# M7050C.net
KiCad netlist of a schematic drawn in EAGLE
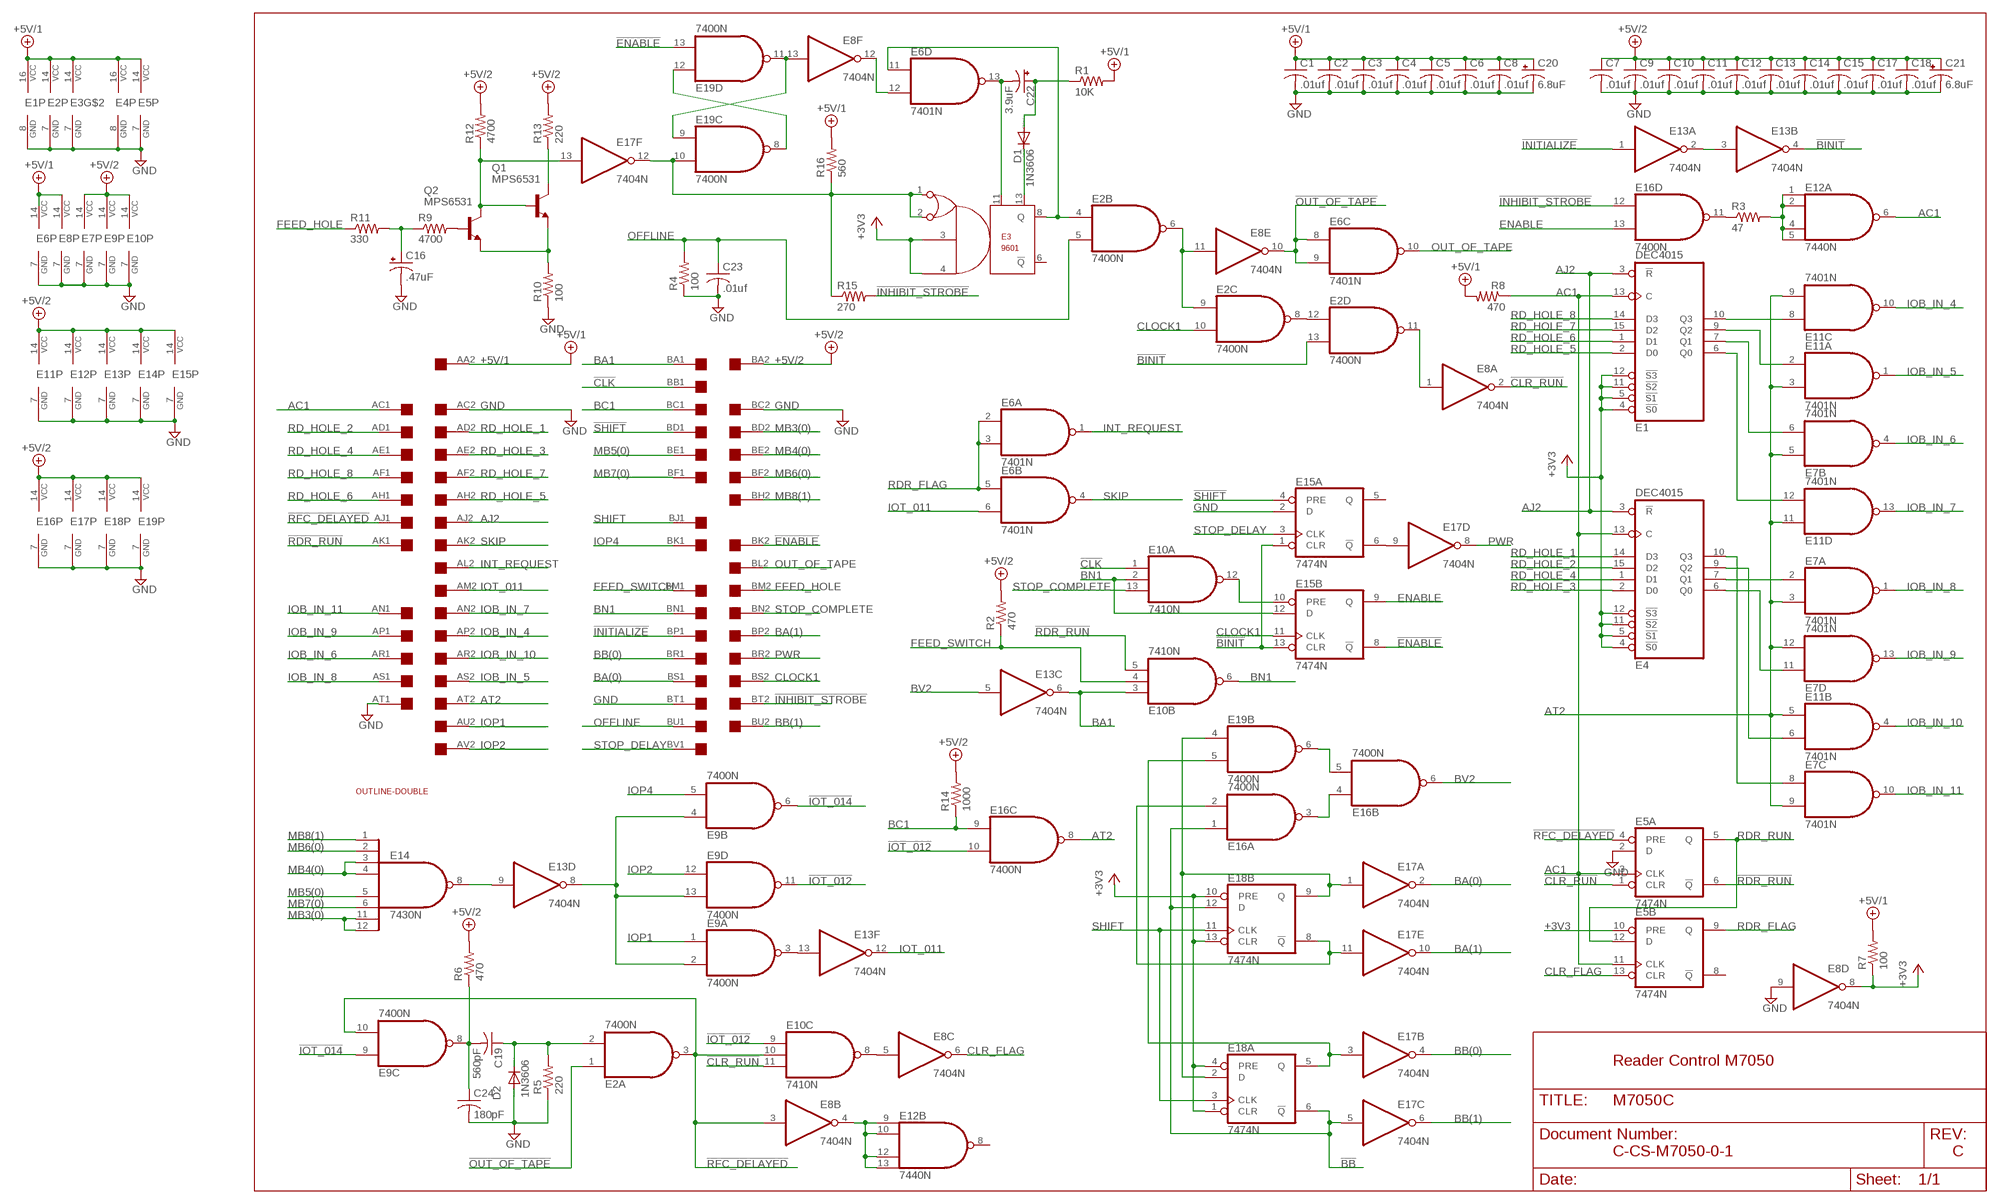
[diagram p0: schematic, sheet 1]

(export (version "E")
  (design (tool "Eeschema 10.0.6"))
  (components
    (comp (ref "C1")
      (value ".01uf")
      (footprint "eagle-import:C075-032X103")
      (libsource (lib "eagle-import") (part "C-US075-032X103"))
    )
    (comp (ref "C2")
      (value ".01uf")
      (footprint "eagle-import:C075-032X103")
      (libsource (lib "eagle-import") (part "C-US075-032X103"))
    )
    (comp (ref "C3")
      (value ".01uf")
      (footprint "eagle-import:C075-032X103")
      (libsource (lib "eagle-import") (part "C-US075-032X103"))
    )
    (comp (ref "C4")
      (value ".01uf")
      (footprint "eagle-import:C075-032X103")
      (libsource (lib "eagle-import") (part "C-US075-032X103"))
    )
    (comp (ref "C5")
      (value ".01uf")
      (footprint "eagle-import:C075-032X103")
      (libsource (lib "eagle-import") (part "C-US075-032X103"))
    )
    (comp (ref "C6")
      (value ".01uf")
      (footprint "eagle-import:C075-032X103")
      (libsource (lib "eagle-import") (part "C-US075-032X103"))
    )
    (comp (ref "C7")
      (value ".01uf")
      (footprint "eagle-import:C075-032X103")
      (libsource (lib "eagle-import") (part "C-US075-032X103"))
    )
    (comp (ref "C8")
      (value ".01uf")
      (footprint "eagle-import:C075-032X103")
      (libsource (lib "eagle-import") (part "C-US075-032X103"))
    )
    (comp (ref "C9")
      (value ".01uf")
      (footprint "eagle-import:C075-032X103")
      (libsource (lib "eagle-import") (part "C-US075-032X103"))
    )
    (comp (ref "C10")
      (value ".01uf")
      (footprint "eagle-import:C075-032X103")
      (libsource (lib "eagle-import") (part "C-US075-032X103"))
    )
    (comp (ref "C11")
      (value ".01uf")
      (footprint "eagle-import:C075-032X103")
      (libsource (lib "eagle-import") (part "C-US075-032X103"))
    )
    (comp (ref "C12")
      (value ".01uf")
      (footprint "eagle-import:C075-032X103")
      (libsource (lib "eagle-import") (part "C-US075-032X103"))
    )
    (comp (ref "C13")
      (value ".01uf")
      (footprint "eagle-import:C075-032X103")
      (libsource (lib "eagle-import") (part "C-US075-032X103"))
    )
    (comp (ref "C14")
      (value ".01uf")
      (footprint "eagle-import:C075-032X103")
      (libsource (lib "eagle-import") (part "C-US075-032X103"))
    )
    (comp (ref "C15")
      (value ".01uf")
      (footprint "eagle-import:C075-032X103")
      (libsource (lib "eagle-import") (part "C-US075-032X103"))
    )
    (comp (ref "C16")
      (value ".47uF")
      (footprint "eagle-import:E15-5")
      (libsource (lib "eagle-import") (part "CPOL-USE15-5AXIAL"))
    )
    (comp (ref "C17")
      (value ".01uf")
      (footprint "eagle-import:C075-032X103")
      (libsource (lib "eagle-import") (part "C-US075-032X103"))
    )
    (comp (ref "C18")
      (value ".01uf")
      (footprint "eagle-import:C075-032X103")
      (libsource (lib "eagle-import") (part "C-US075-032X103"))
    )
    (comp (ref "C19")
      (value "560pF")
      (footprint "eagle-import:C075-032X103")
      (libsource (lib "eagle-import") (part "C-US075-032X103"))
    )
    (comp (ref "C20")
      (value "6.8uF")
      (footprint "eagle-import:E12-8")
      (libsource (lib "eagle-import") (part "CPOL-USE20-8AXIAL"))
    )
    (comp (ref "C21")
      (value "6.8uF")
      (footprint "eagle-import:E12-8")
      (libsource (lib "eagle-import") (part "CPOL-USE20-8AXIAL"))
    )
    (comp (ref "C22")
      (value "3.9uF")
      (footprint "eagle-import:E15-5")
      (libsource (lib "eagle-import") (part "rcl_CPOL-USE15-5AXIAL"))
    )
    (comp (ref "C23")
      (value ".01uf")
      (footprint "eagle-import:C075-032X103")
      (libsource (lib "eagle-import") (part "C-US075-032X103"))
    )
    (comp (ref "C24")
      (value "180pF")
      (footprint "eagle-import:C075-032X103")
      (libsource (lib "eagle-import") (part "C-US075-032X103"))
    )
    (comp (ref "D1")
      (value "1N3606")
      (footprint "eagle-import:DO35-10")
      (libsource (lib "eagle-import") (part "1N4148DO35-10"))
    )
    (comp (ref "D2")
      (value "1N3606")
      (footprint "eagle-import:DO35-10")
      (libsource (lib "eagle-import") (part "1N4148DO35-10"))
    )
    (comp (ref "E1")
      (value "DEC4015")
      (footprint "eagle-import:DIL16")
      (libsource (lib "eagle-import") (part "DEC4015"))
    )
    (comp (ref "E2")
      (value "7400N")
      (footprint "eagle-import:DIL14")
      (libsource (lib "eagle-import") (part "7400N"))
    )
    (comp (ref "E3")
      (value "9601")
      (footprint "eagle-import:DIL14")
      (libsource (lib "eagle-import") (part "9601"))
    )
    (comp (ref "E4")
      (value "DEC4015")
      (footprint "eagle-import:DIL16")
      (libsource (lib "eagle-import") (part "DEC4015"))
    )
    (comp (ref "E5")
      (value "7474N")
      (footprint "eagle-import:DIL14")
      (libsource (lib "eagle-import") (part "7474NS"))
    )
    (comp (ref "E6")
      (value "7401N")
      (footprint "eagle-import:DIL14")
      (libsource (lib "eagle-import") (part "7401NLS"))
    )
    (comp (ref "E7")
      (value "7401N")
      (footprint "eagle-import:DIL14")
      (libsource (lib "eagle-import") (part "7401NLS"))
    )
    (comp (ref "E8")
      (value "7404N")
      (footprint "eagle-import:DIL14")
      (libsource (lib "eagle-import") (part "7404N"))
    )
    (comp (ref "E9")
      (value "7400N")
      (footprint "eagle-import:DIL14")
      (libsource (lib "eagle-import") (part "7400N"))
    )
    (comp (ref "E10")
      (value "7410N")
      (footprint "eagle-import:DIL14")
      (libsource (lib "eagle-import") (part "7410N"))
    )
    (comp (ref "E11")
      (value "7401N")
      (footprint "eagle-import:DIL14")
      (libsource (lib "eagle-import") (part "7401NLS"))
    )
    (comp (ref "E12")
      (value "7440N")
      (footprint "eagle-import:DIL14")
      (libsource (lib "eagle-import") (part "7420NS"))
    )
    (comp (ref "E13")
      (value "7404N")
      (footprint "eagle-import:DIL14")
      (libsource (lib "eagle-import") (part "7404N"))
    )
    (comp (ref "E14")
      (value "7430N")
      (footprint "eagle-import:DIL14")
      (libsource (lib "eagle-import") (part "7430N"))
    )
    (comp (ref "E15")
      (value "7474N")
      (footprint "eagle-import:DIL14")
      (libsource (lib "eagle-import") (part "7474NS"))
    )
    (comp (ref "E16")
      (value "7400N")
      (footprint "eagle-import:DIL14")
      (libsource (lib "eagle-import") (part "7400N"))
    )
    (comp (ref "E17")
      (value "7404N")
      (footprint "eagle-import:DIL14")
      (libsource (lib "eagle-import") (part "7404N"))
    )
    (comp (ref "E18")
      (value "7474N")
      (footprint "eagle-import:DIL14")
      (libsource (lib "eagle-import") (part "7474NS"))
    )
    (comp (ref "E19")
      (value "7400N")
      (footprint "eagle-import:DIL14")
      (libsource (lib "eagle-import") (part "7400N"))
    )
    (comp (ref "Q1")
      (value "MPS6531")
      (footprint "eagle-import:TO5")
      (libsource (lib "eagle-import") (part "2N2102"))
    )
    (comp (ref "Q2")
      (value "MPS6531")
      (footprint "eagle-import:TO5")
      (libsource (lib "eagle-import") (part "2N2102"))
    )
    (comp (ref "R1")
      (value "10K")
      (footprint "eagle-import:0207_10")
      (libsource (lib "eagle-import") (part "R-US_0207/10"))
    )
    (comp (ref "R2")
      (value "470")
      (footprint "eagle-import:0207_10")
      (libsource (lib "eagle-import") (part "R-US_0207/10"))
    )
    (comp (ref "R3")
      (value "47")
      (footprint "eagle-import:0207_10")
      (libsource (lib "eagle-import") (part "R-US_0207/10"))
    )
    (comp (ref "R4")
      (value "100")
      (footprint "eagle-import:0207_10")
      (libsource (lib "eagle-import") (part "R-US_0207/10"))
    )
    (comp (ref "R5")
      (value "220")
      (footprint "eagle-import:0207_10")
      (libsource (lib "eagle-import") (part "R-US_0207/10"))
    )
    (comp (ref "R6")
      (value "470")
      (footprint "eagle-import:0207_10")
      (libsource (lib "eagle-import") (part "R-US_0207/10"))
    )
    (comp (ref "R7")
      (value "100")
      (footprint "eagle-import:0207_10")
      (libsource (lib "eagle-import") (part "R-US_0207/10"))
    )
    (comp (ref "R8")
      (value "470")
      (footprint "eagle-import:0207_10")
      (libsource (lib "eagle-import") (part "R-US_0207/10"))
    )
    (comp (ref "R9")
      (value "4700")
      (footprint "eagle-import:0207_10")
      (libsource (lib "eagle-import") (part "R-US_0207/10"))
    )
    (comp (ref "R10")
      (value "100")
      (footprint "eagle-import:0207_10")
      (libsource (lib "eagle-import") (part "R-US_0207/10"))
    )
    (comp (ref "R11")
      (value "330")
      (footprint "eagle-import:0207_10")
      (libsource (lib "eagle-import") (part "R-US_0207/10"))
    )
    (comp (ref "R12")
      (value "4700")
      (footprint "eagle-import:0207_10")
      (libsource (lib "eagle-import") (part "R-US_0207/10"))
    )
    (comp (ref "R13")
      (value "220")
      (footprint "eagle-import:0207_10")
      (libsource (lib "eagle-import") (part "R-US_0207/10"))
    )
    (comp (ref "R14")
      (value "1000")
      (footprint "eagle-import:0207_10")
      (libsource (lib "eagle-import") (part "R-US_0207/10"))
    )
    (comp (ref "R15")
      (value "270")
      (footprint "eagle-import:0207_10")
      (libsource (lib "eagle-import") (part "R-US_0207/10"))
    )
    (comp (ref "R16")
      (value "560")
      (footprint "eagle-import:0207_10")
      (libsource (lib "eagle-import") (part "R-US_0207/10"))
    )
    (comp (ref "U$5")
      (value "DOUBLE")
      (footprint "eagle-import:EDGE-CON4")
      (libsource (lib "eagle-import") (part "DOUBLE"))
    )
    (comp (ref "U$6")
      (value "OUTLINE-DOUBLE")
      (footprint "eagle-import:DOUBLE")
      (libsource (lib "eagle-import") (part "OUTLINE-DOUBLE"))
    )
  )
  (nets
    (net (code "1") (name "+3V3") (class "Default")
      (node (ref "E1") (pin "11") (pinfunction "~{S2}_11") (pintype "input"))
      (node (ref "E1") (pin "12") (pinfunction "~{S3}_12") (pintype "input"))
      (node (ref "E1") (pin "4") (pinfunction "~{S0}_4") (pintype "input"))
      (node (ref "E1") (pin "5") (pinfunction "~{S1}_5") (pintype "input"))
      (node (ref "E18") (pin "1") (pinfunction "CLR_1") (pintype "input"))
      (node (ref "E18") (pin "10") (pinfunction "PRE_10") (pintype "input"))
      (node (ref "E18") (pin "13") (pinfunction "CLR_13") (pintype "input"))
      (node (ref "E18") (pin "4") (pinfunction "PRE_4") (pintype "input"))
      (node (ref "E3") (pin "3") (pinfunction "P$3_3") (pintype "input"))
      (node (ref "E3") (pin "4") (pinfunction "P$4_4") (pintype "input"))
      (node (ref "E4") (pin "11") (pinfunction "~{S2}_11") (pintype "input"))
      (node (ref "E4") (pin "12") (pinfunction "~{S3}_12") (pintype "input"))
      (node (ref "E4") (pin "4") (pinfunction "~{S0}_4") (pintype "input"))
      (node (ref "E4") (pin "5") (pinfunction "~{S1}_5") (pintype "input"))
      (node (ref "E5") (pin "10") (pinfunction "PRE_10") (pintype "input"))
      (node (ref "E8") (pin "8") (pinfunction "O_8") (pintype "output"))
      (node (ref "R7") (pin "1") (pinfunction "1_1") (pintype "passive"))
    )
    (net (code "2") (name "+5V{slash}1") (class "Default")
      (node (ref "C1") (pin "1") (pinfunction "1_1") (pintype "passive"))
      (node (ref "C2") (pin "1") (pinfunction "1_1") (pintype "passive"))
      (node (ref "C20") (pin "+") (pinfunction "+_+") (pintype "passive"))
      (node (ref "C3") (pin "1") (pinfunction "1_1") (pintype "passive"))
      (node (ref "C4") (pin "1") (pinfunction "1_1") (pintype "passive"))
      (node (ref "C5") (pin "1") (pinfunction "1_1") (pintype "passive"))
      (node (ref "C6") (pin "1") (pinfunction "1_1") (pintype "passive"))
      (node (ref "C8") (pin "1") (pinfunction "1_1") (pintype "passive"))
      (node (ref "E1") (pin "16") (pinfunction "VCC_16") (pintype "power_in"))
      (node (ref "E2") (pin "14") (pinfunction "VCC_14") (pintype "power_in"))
      (node (ref "E3") (pin "14") (pinfunction "VCC_14") (pintype "power_in"))
      (node (ref "E4") (pin "16") (pinfunction "VCC_16") (pintype "power_in"))
      (node (ref "E5") (pin "14") (pinfunction "VCC_14") (pintype "power_in"))
      (node (ref "E6") (pin "14") (pinfunction "VCC_14") (pintype "power_in"))
      (node (ref "E8") (pin "14") (pinfunction "VCC_14") (pintype "power_in"))
      (node (ref "R1") (pin "2") (pinfunction "2_2") (pintype "passive"))
      (node (ref "R16") (pin "2") (pinfunction "2_2") (pintype "passive"))
      (node (ref "R7") (pin "2") (pinfunction "2_2") (pintype "passive"))
      (node (ref "R8") (pin "2") (pinfunction "2_2") (pintype "passive"))
      (node (ref "U$5") (pin "AA2") (pinfunction "1_AA2") (pintype "bidirectional"))
    )
    (net (code "3") (name "+5V{slash}2") (class "Default")
      (node (ref "C10") (pin "1") (pinfunction "1_1") (pintype "passive"))
      (node (ref "C11") (pin "1") (pinfunction "1_1") (pintype "passive"))
      (node (ref "C12") (pin "1") (pinfunction "1_1") (pintype "passive"))
      (node (ref "C13") (pin "1") (pinfunction "1_1") (pintype "passive"))
      (node (ref "C14") (pin "1") (pinfunction "1_1") (pintype "passive"))
      (node (ref "C15") (pin "1") (pinfunction "1_1") (pintype "passive"))
      (node (ref "C17") (pin "1") (pinfunction "1_1") (pintype "passive"))
      (node (ref "C18") (pin "1") (pinfunction "1_1") (pintype "passive"))
      (node (ref "C21") (pin "+") (pinfunction "+_+") (pintype "passive"))
      (node (ref "C7") (pin "1") (pinfunction "1_1") (pintype "passive"))
      (node (ref "C9") (pin "1") (pinfunction "1_1") (pintype "passive"))
      (node (ref "E10") (pin "14") (pinfunction "VCC_14") (pintype "power_in"))
      (node (ref "E11") (pin "14") (pinfunction "VCC_14") (pintype "power_in"))
      (node (ref "E12") (pin "14") (pinfunction "VCC_14") (pintype "power_in"))
      (node (ref "E13") (pin "14") (pinfunction "VCC_14") (pintype "power_in"))
      (node (ref "E14") (pin "14") (pinfunction "VCC_14") (pintype "power_in"))
      (node (ref "E15") (pin "14") (pinfunction "VCC_14") (pintype "power_in"))
      (node (ref "E16") (pin "14") (pinfunction "VCC_14") (pintype "power_in"))
      (node (ref "E17") (pin "14") (pinfunction "VCC_14") (pintype "power_in"))
      (node (ref "E18") (pin "14") (pinfunction "VCC_14") (pintype "power_in"))
      (node (ref "E19") (pin "14") (pinfunction "VCC_14") (pintype "power_in"))
      (node (ref "E7") (pin "14") (pinfunction "VCC_14") (pintype "power_in"))
      (node (ref "E9") (pin "14") (pinfunction "VCC_14") (pintype "power_in"))
      (node (ref "R12") (pin "2") (pinfunction "2_2") (pintype "passive"))
      (node (ref "R13") (pin "2") (pinfunction "2_2") (pintype "passive"))
      (node (ref "R14") (pin "2") (pinfunction "2_2") (pintype "passive"))
      (node (ref "R2") (pin "2") (pinfunction "2_2") (pintype "passive"))
      (node (ref "R6") (pin "2") (pinfunction "2_2") (pintype "passive"))
      (node (ref "U$5") (pin "BA2") (pinfunction "1_BA2") (pintype "bidirectional"))
    )
    (net (code "4") (name "/AC1") (class "Default")
      (node (ref "E1") (pin "13") (pinfunction "C_13") (pintype "bidirectional"))
      (node (ref "E12") (pin "6") (pinfunction "O_6") (pintype "output"))
      (node (ref "E4") (pin "13") (pinfunction "C_13") (pintype "bidirectional"))
      (node (ref "E5") (pin "11") (pinfunction "CLK_11") (pintype "input"))
      (node (ref "E5") (pin "3") (pinfunction "CLK_3") (pintype "input"))
      (node (ref "R8") (pin "1") (pinfunction "1_1") (pintype "passive"))
      (node (ref "U$5") (pin "AC1") (pinfunction "1_AC1") (pintype "bidirectional"))
    )
    (net (code "5") (name "/AJ2") (class "Default")
      (node (ref "E1") (pin "3") (pinfunction "~{R}_3") (pintype "input"))
      (node (ref "E4") (pin "3") (pinfunction "~{R}_3") (pintype "input"))
      (node (ref "U$5") (pin "AJ2") (pinfunction "1_AJ2") (pintype "bidirectional"))
    )
    (net (code "6") (name "/AT2") (class "Default")
      (node (ref "E11") (pin "11") (pinfunction "I0_11") (pintype "input"))
      (node (ref "E11") (pin "3") (pinfunction "I1_3") (pintype "input"))
      (node (ref "E11") (pin "5") (pinfunction "I0_5") (pintype "input"))
      (node (ref "E11") (pin "9") (pinfunction "I1_9") (pintype "input"))
      (node (ref "E16") (pin "8") (pinfunction "O_8") (pintype "output"))
      (node (ref "E7") (pin "12") (pinfunction "I1_12") (pintype "input"))
      (node (ref "E7") (pin "3") (pinfunction "I1_3") (pintype "input"))
      (node (ref "E7") (pin "5") (pinfunction "I0_5") (pintype "input"))
      (node (ref "E7") (pin "9") (pinfunction "I1_9") (pintype "input"))
      (node (ref "U$5") (pin "AT2") (pinfunction "1_AT2") (pintype "bidirectional"))
    )
    (net (code "7") (name "/BA(0)") (class "Default")
      (node (ref "E17") (pin "2") (pinfunction "O_2") (pintype "output"))
      (node (ref "U$5") (pin "BS1") (pinfunction "1_BS1") (pintype "bidirectional"))
    )
    (net (code "8") (name "/BA(1)") (class "Default")
      (node (ref "E17") (pin "10") (pinfunction "O_10") (pintype "output"))
      (node (ref "U$5") (pin "BP2") (pinfunction "1_BP2") (pintype "bidirectional"))
    )
    (net (code "9") (name "/BA1") (class "Default")
      (node (ref "E10") (pin "3") (pinfunction "I0_3") (pintype "input"))
      (node (ref "E13") (pin "6") (pinfunction "O_6") (pintype "output"))
      (node (ref "U$5") (pin "BA1") (pinfunction "1_BA1") (pintype "bidirectional"))
    )
    (net (code "10") (name "/BB(0)") (class "Default")
      (node (ref "E17") (pin "4") (pinfunction "O_4") (pintype "output"))
      (node (ref "U$5") (pin "BR1") (pinfunction "1_BR1") (pintype "bidirectional"))
    )
    (net (code "11") (name "/BB(1)") (class "Default")
      (node (ref "E17") (pin "6") (pinfunction "O_6") (pintype "output"))
      (node (ref "U$5") (pin "BU2") (pinfunction "1_BU2") (pintype "bidirectional"))
    )
    (net (code "12") (name "/BC1") (class "Default")
      (node (ref "E16") (pin "9") (pinfunction "I0_9") (pintype "input"))
      (node (ref "R14") (pin "1") (pinfunction "1_1") (pintype "passive"))
      (node (ref "U$5") (pin "BC1") (pinfunction "1_BC1") (pintype "bidirectional"))
    )
    (net (code "13") (name "/BN1") (class "Default")
      (node (ref "E10") (pin "2") (pinfunction "I1_2") (pintype "input"))
      (node (ref "E10") (pin "6") (pinfunction "O_6") (pintype "output"))
      (node (ref "E15") (pin "12") (pinfunction "D_12") (pintype "input"))
      (node (ref "U$5") (pin "BN1") (pinfunction "1_BN1") (pintype "bidirectional"))
    )
    (net (code "14") (name "/BV2") (class "Default")
      (node (ref "E13") (pin "5") (pinfunction "I_5") (pintype "input"))
      (node (ref "E16") (pin "6") (pinfunction "O_6") (pintype "output"))
    )
    (net (code "15") (name "/CLOCK1") (class "Default")
      (node (ref "E15") (pin "11") (pinfunction "CLK_11") (pintype "input"))
      (node (ref "E2") (pin "10") (pinfunction "I1_10") (pintype "input"))
      (node (ref "U$5") (pin "BS2") (pinfunction "1_BS2") (pintype "bidirectional"))
    )
    (net (code "16") (name "/CLR_FLAG") (class "Default")
      (node (ref "E5") (pin "13") (pinfunction "CLR_13") (pintype "input"))
      (node (ref "E8") (pin "6") (pinfunction "O_6") (pintype "output"))
    )
    (net (code "17") (name "/ENABLE") (class "Default")
      (node (ref "E15") (pin "9") (pinfunction "Q_9") (pintype "output"))
      (node (ref "E16") (pin "13") (pinfunction "I1_13") (pintype "input"))
    )
    (net (code "18") (name "/FEED_HOLE") (class "Default")
      (node (ref "R11") (pin "1") (pinfunction "1_1") (pintype "passive"))
      (node (ref "U$5") (pin "BM2") (pinfunction "1_BM2") (pintype "bidirectional"))
    )
    (net (code "19") (name "/FEED_SWITCH") (class "Default")
      (node (ref "E10") (pin "4") (pinfunction "I1_4") (pintype "input"))
      (node (ref "R2") (pin "1") (pinfunction "1_1") (pintype "passive"))
      (node (ref "U$5") (pin "BM1") (pinfunction "1_BM1") (pintype "bidirectional"))
    )
    (net (code "20") (name "/INT_REQUEST") (class "Default")
      (node (ref "E6") (pin "1") (pinfunction "O_1") (pintype "open_collector"))
      (node (ref "U$5") (pin "AL2") (pinfunction "1_AL2") (pintype "bidirectional"))
    )
    (net (code "21") (name "/IOB_IN_4") (class "Default")
      (node (ref "E11") (pin "10") (pinfunction "O_10") (pintype "open_collector"))
      (node (ref "U$5") (pin "AP2") (pinfunction "1_AP2") (pintype "bidirectional"))
    )
    (net (code "22") (name "/IOB_IN_5") (class "Default")
      (node (ref "E11") (pin "1") (pinfunction "O_1") (pintype "open_collector"))
      (node (ref "U$5") (pin "AS2") (pinfunction "1_AS2") (pintype "bidirectional"))
    )
    (net (code "23") (name "/IOB_IN_6") (class "Default")
      (node (ref "E7") (pin "4") (pinfunction "O_4") (pintype "open_collector"))
      (node (ref "U$5") (pin "AR1") (pinfunction "1_AR1") (pintype "bidirectional"))
    )
    (net (code "24") (name "/IOB_IN_7") (class "Default")
      (node (ref "E11") (pin "13") (pinfunction "O_13") (pintype "open_collector"))
      (node (ref "U$5") (pin "AN2") (pinfunction "1_AN2") (pintype "bidirectional"))
    )
    (net (code "25") (name "/IOB_IN_8") (class "Default")
      (node (ref "E7") (pin "1") (pinfunction "O_1") (pintype "open_collector"))
      (node (ref "U$5") (pin "AS1") (pinfunction "1_AS1") (pintype "bidirectional"))
    )
    (net (code "26") (name "/IOB_IN_9") (class "Default")
      (node (ref "E7") (pin "13") (pinfunction "O_13") (pintype "open_collector"))
      (node (ref "U$5") (pin "AP1") (pinfunction "1_AP1") (pintype "bidirectional"))
    )
    (net (code "27") (name "/IOB_IN_10") (class "Default")
      (node (ref "E11") (pin "4") (pinfunction "O_4") (pintype "open_collector"))
      (node (ref "U$5") (pin "AR2") (pinfunction "1_AR2") (pintype "bidirectional"))
    )
    (net (code "28") (name "/IOB_IN_11") (class "Default")
      (node (ref "E7") (pin "10") (pinfunction "O_10") (pintype "open_collector"))
      (node (ref "U$5") (pin "AN1") (pinfunction "1_AN1") (pintype "bidirectional"))
    )
    (net (code "29") (name "/IOP1") (class "Default")
      (node (ref "E9") (pin "1") (pinfunction "I0_1") (pintype "input"))
      (node (ref "U$5") (pin "AU2") (pinfunction "1_AU2") (pintype "bidirectional"))
    )
    (net (code "30") (name "/IOP2") (class "Default")
      (node (ref "E9") (pin "12") (pinfunction "I0_12") (pintype "input"))
      (node (ref "U$5") (pin "AV2") (pinfunction "1_AV2") (pintype "bidirectional"))
    )
    (net (code "31") (name "/IOP4") (class "Default")
      (node (ref "E9") (pin "5") (pinfunction "I1_5") (pintype "input"))
      (node (ref "U$5") (pin "BK1") (pinfunction "1_BK1") (pintype "bidirectional"))
    )
    (net (code "32") (name "/IOT_011") (class "Default")
      (node (ref "E13") (pin "12") (pinfunction "O_12") (pintype "output"))
      (node (ref "E6") (pin "6") (pinfunction "I1_6") (pintype "input"))
      (node (ref "U$5") (pin "AM2") (pinfunction "1_AM2") (pintype "bidirectional"))
    )
    (net (code "33") (name "/MB3(0)") (class "Default")
      (node (ref "E14") (pin "11") (pinfunction "I6_11") (pintype "input"))
      (node (ref "E14") (pin "12") (pinfunction "I7_12") (pintype "input"))
      (node (ref "U$5") (pin "BD2") (pinfunction "1_BD2") (pintype "bidirectional"))
    )
    (net (code "34") (name "/MB4(0)") (class "Default")
      (node (ref "E14") (pin "3") (pinfunction "I2_3") (pintype "input"))
      (node (ref "E14") (pin "4") (pinfunction "I3_4") (pintype "input"))
      (node (ref "U$5") (pin "BE2") (pinfunction "1_BE2") (pintype "bidirectional"))
    )
    (net (code "35") (name "/MB5(0)") (class "Default")
      (node (ref "E14") (pin "5") (pinfunction "I4_5") (pintype "input"))
      (node (ref "U$5") (pin "BE1") (pinfunction "1_BE1") (pintype "bidirectional"))
    )
    (net (code "36") (name "/MB6(0)") (class "Default")
      (node (ref "E14") (pin "2") (pinfunction "I1_2") (pintype "input"))
      (node (ref "U$5") (pin "BF2") (pinfunction "1_BF2") (pintype "bidirectional"))
    )
    (net (code "37") (name "/MB7(0)") (class "Default")
      (node (ref "E14") (pin "6") (pinfunction "I5_6") (pintype "input"))
      (node (ref "U$5") (pin "BF1") (pinfunction "1_BF1") (pintype "bidirectional"))
    )
    (net (code "38") (name "/MB8(1)") (class "Default")
      (node (ref "E14") (pin "1") (pinfunction "I0_1") (pintype "input"))
      (node (ref "U$5") (pin "BH2") (pinfunction "1_BH2") (pintype "bidirectional"))
    )
    (net (code "39") (name "/OFFLINE") (class "Default")
      (node (ref "C23") (pin "1") (pinfunction "1_1") (pintype "passive"))
      (node (ref "E2") (pin "5") (pinfunction "I1_5") (pintype "input"))
      (node (ref "R4") (pin "2") (pinfunction "2_2") (pintype "passive"))
      (node (ref "U$5") (pin "BU1") (pinfunction "1_BU1") (pintype "bidirectional"))
    )
    (net (code "40") (name "/OUT_OF_TAPE") (class "Default")
      (node (ref "E6") (pin "10") (pinfunction "O_10") (pintype "open_collector"))
      (node (ref "U$5") (pin "BL2") (pinfunction "1_BL2") (pintype "bidirectional"))
    )
    (net (code "41") (name "/PWR") (class "Default")
      (node (ref "E17") (pin "8") (pinfunction "O_8") (pintype "output"))
      (node (ref "U$5") (pin "BR2") (pinfunction "1_BR2") (pintype "bidirectional"))
    )
    (net (code "42") (name "/RDR_FLAG") (class "Default")
      (node (ref "E5") (pin "9") (pinfunction "Q_9") (pintype "output"))
      (node (ref "E6") (pin "2") (pinfunction "I0_2") (pintype "input"))
      (node (ref "E6") (pin "3") (pinfunction "I1_3") (pintype "input"))
      (node (ref "E6") (pin "5") (pinfunction "I0_5") (pintype "input"))
    )
    (net (code "43") (name "/RDR_RUN") (class "Default")
      (node (ref "E5") (pin "12") (pinfunction "D_12") (pintype "input"))
      (node (ref "E5") (pin "5") (pinfunction "Q_5") (pintype "output"))
    )
    (net (code "44") (name "/RD_HOLE_1") (class "Default")
      (node (ref "E4") (pin "14") (pinfunction "D3_14") (pintype "input"))
      (node (ref "U$5") (pin "AD2") (pinfunction "1_AD2") (pintype "bidirectional"))
    )
    (net (code "45") (name "/RD_HOLE_2") (class "Default")
      (node (ref "E4") (pin "15") (pinfunction "D2_15") (pintype "input"))
      (node (ref "U$5") (pin "AD1") (pinfunction "1_AD1") (pintype "bidirectional"))
    )
    (net (code "46") (name "/RD_HOLE_3") (class "Default")
      (node (ref "E4") (pin "2") (pinfunction "D0_2") (pintype "input"))
      (node (ref "U$5") (pin "AE2") (pinfunction "1_AE2") (pintype "bidirectional"))
    )
    (net (code "47") (name "/RD_HOLE_4") (class "Default")
      (node (ref "E4") (pin "1") (pinfunction "D1_1") (pintype "input"))
      (node (ref "U$5") (pin "AE1") (pinfunction "1_AE1") (pintype "bidirectional"))
    )
    (net (code "48") (name "/RD_HOLE_5") (class "Default")
      (node (ref "E1") (pin "2") (pinfunction "D0_2") (pintype "input"))
      (node (ref "U$5") (pin "AH2") (pinfunction "1_AH2") (pintype "bidirectional"))
    )
    (net (code "49") (name "/RD_HOLE_6") (class "Default")
      (node (ref "E1") (pin "1") (pinfunction "D1_1") (pintype "input"))
      (node (ref "U$5") (pin "AH1") (pinfunction "1_AH1") (pintype "bidirectional"))
    )
    (net (code "50") (name "/RD_HOLE_7") (class "Default")
      (node (ref "E1") (pin "15") (pinfunction "D2_15") (pintype "input"))
      (node (ref "U$5") (pin "AF2") (pinfunction "1_AF2") (pintype "bidirectional"))
    )
    (net (code "51") (name "/RD_HOLE_8") (class "Default")
      (node (ref "E1") (pin "14") (pinfunction "D3_14") (pintype "input"))
      (node (ref "U$5") (pin "AF1") (pinfunction "1_AF1") (pintype "bidirectional"))
    )
    (net (code "52") (name "/SHIFT") (class "Default")
      (node (ref "E18") (pin "11") (pinfunction "CLK_11") (pintype "input"))
      (node (ref "E18") (pin "3") (pinfunction "CLK_3") (pintype "input"))
      (node (ref "U$5") (pin "BJ1") (pinfunction "1_BJ1") (pintype "bidirectional"))
    )
    (net (code "53") (name "/SKIP") (class "Default")
      (node (ref "E6") (pin "4") (pinfunction "O_4") (pintype "open_collector"))
      (node (ref "U$5") (pin "AK2") (pinfunction "1_AK2") (pintype "bidirectional"))
    )
    (net (code "54") (name "/STOP_COMPLETE") (class "Default")
      (node (ref "E10") (pin "13") (pinfunction "I2_13") (pintype "input"))
      (node (ref "U$5") (pin "BN2") (pinfunction "1_BN2") (pintype "bidirectional"))
    )
    (net (code "55") (name "/STOP_DELAY") (class "Default")
      (node (ref "E15") (pin "3") (pinfunction "CLK_3") (pintype "input"))
      (node (ref "U$5") (pin "BV1") (pinfunction "1_BV1") (pintype "bidirectional"))
    )
    (net (code "56") (name "/~{BB}") (class "Default")
      (node (ref "E16") (pin "1") (pinfunction "I0_1") (pintype "input"))
      (node (ref "E17") (pin "5") (pinfunction "I_5") (pintype "input"))
      (node (ref "E18") (pin "12") (pinfunction "D_12") (pintype "input"))
      (node (ref "E18") (pin "6") (pinfunction "~{Q}_6") (pintype "output"))
    )
    (net (code "57") (name "/~{BINIT}") (class "Default")
      (node (ref "E13") (pin "4") (pinfunction "O_4") (pintype "output"))
      (node (ref "E15") (pin "1") (pinfunction "CLR_1") (pintype "input"))
      (node (ref "E15") (pin "13") (pinfunction "CLR_13") (pintype "input"))
      (node (ref "E2") (pin "13") (pinfunction "I1_13") (pintype "input"))
    )
    (net (code "58") (name "/~{CLK}") (class "Default")
      (node (ref "E10") (pin "1") (pinfunction "I0_1") (pintype "input"))
      (node (ref "U$5") (pin "BB1") (pinfunction "1_BB1") (pintype "bidirectional"))
    )
    (net (code "59") (name "/~{CLR_RUN}") (class "Default")
      (node (ref "E10") (pin "11") (pinfunction "I2_11") (pintype "input"))
      (node (ref "E5") (pin "1") (pinfunction "CLR_1") (pintype "input"))
      (node (ref "E8") (pin "2") (pinfunction "O_2") (pintype "output"))
    )
    (net (code "60") (name "/~{ENABLE}") (class "Default")
      (node (ref "E15") (pin "8") (pinfunction "~{Q}_8") (pintype "output"))
      (node (ref "E19") (pin "13") (pinfunction "I1_13") (pintype "input"))
      (node (ref "U$5") (pin "BK2") (pinfunction "1_BK2") (pintype "bidirectional"))
    )
    (net (code "61") (name "/~{INHIBIT_STROBE}") (class "Default")
      (node (ref "E16") (pin "12") (pinfunction "I0_12") (pintype "input"))
      (node (ref "R15") (pin "2") (pinfunction "2_2") (pintype "passive"))
      (node (ref "U$5") (pin "BT2") (pinfunction "1_BT2") (pintype "bidirectional"))
    )
    (net (code "62") (name "/~{INITIALIZE}") (class "Default")
      (node (ref "E13") (pin "1") (pinfunction "I_1") (pintype "input"))
      (node (ref "U$5") (pin "BP1") (pinfunction "1_BP1") (pintype "bidirectional"))
    )
    (net (code "63") (name "/~{IOT_012}") (class "Default")
      (node (ref "E10") (pin "9") (pinfunction "I0_9") (pintype "input"))
      (node (ref "E16") (pin "10") (pinfunction "I1_10") (pintype "input"))
      (node (ref "E9") (pin "11") (pinfunction "O_11") (pintype "output"))
    )
    (net (code "64") (name "/~{IOT_014}") (class "Default")
      (node (ref "E9") (pin "6") (pinfunction "O_6") (pintype "output"))
      (node (ref "E9") (pin "9") (pinfunction "I0_9") (pintype "input"))
    )
    (net (code "65") (name "/~{OUT_OF_TAPE}") (class "Default")
      (node (ref "E2") (pin "1") (pinfunction "I0_1") (pintype "input"))
      (node (ref "E6") (pin "8") (pinfunction "I0_8") (pintype "input"))
      (node (ref "E6") (pin "9") (pinfunction "I1_9") (pintype "input"))
      (node (ref "E8") (pin "10") (pinfunction "O_10") (pintype "output"))
    )
    (net (code "66") (name "/~{RDR_RUN}") (class "Default")
      (node (ref "E10") (pin "5") (pinfunction "I2_5") (pintype "input"))
      (node (ref "E5") (pin "6") (pinfunction "~{Q}_6") (pintype "output"))
      (node (ref "U$5") (pin "AK1") (pinfunction "1_AK1") (pintype "bidirectional"))
    )
    (net (code "67") (name "/~{RFC_DELAYED}") (class "Default")
      (node (ref "E10") (pin "10") (pinfunction "I1_10") (pintype "input"))
      (node (ref "E2") (pin "3") (pinfunction "O_3") (pintype "output"))
      (node (ref "E5") (pin "4") (pinfunction "PRE_4") (pintype "input"))
      (node (ref "E8") (pin "3") (pinfunction "I_3") (pintype "input"))
      (node (ref "E9") (pin "10") (pinfunction "I1_10") (pintype "input"))
      (node (ref "U$5") (pin "AJ1") (pinfunction "1_AJ1") (pintype "bidirectional"))
    )
    (net (code "68") (name "/~{SHIFT}") (class "Default")
      (node (ref "E15") (pin "4") (pinfunction "PRE_4") (pintype "input"))
      (node (ref "U$5") (pin "BD1") (pinfunction "1_BD1") (pintype "bidirectional"))
    )
    (net (code "69") (name "GND") (class "Default")
      (node (ref "C1") (pin "2") (pinfunction "2_2") (pintype "passive"))
      (node (ref "C10") (pin "2") (pinfunction "2_2") (pintype "passive"))
      (node (ref "C11") (pin "2") (pinfunction "2_2") (pintype "passive"))
      (node (ref "C12") (pin "2") (pinfunction "2_2") (pintype "passive"))
      (node (ref "C13") (pin "2") (pinfunction "2_2") (pintype "passive"))
      (node (ref "C14") (pin "2") (pinfunction "2_2") (pintype "passive"))
      (node (ref "C15") (pin "2") (pinfunction "2_2") (pintype "passive"))
      (node (ref "C16") (pin "-") (pinfunction "-_-") (pintype "passive"))
      (node (ref "C17") (pin "2") (pinfunction "2_2") (pintype "passive"))
      (node (ref "C18") (pin "2") (pinfunction "2_2") (pintype "passive"))
      (node (ref "C2") (pin "2") (pinfunction "2_2") (pintype "passive"))
      (node (ref "C20") (pin "-") (pinfunction "-_-") (pintype "passive"))
      (node (ref "C21") (pin "-") (pinfunction "-_-") (pintype "passive"))
      (node (ref "C23") (pin "2") (pinfunction "2_2") (pintype "passive"))
      (node (ref "C24") (pin "2") (pinfunction "2_2") (pintype "passive"))
      (node (ref "C3") (pin "2") (pinfunction "2_2") (pintype "passive"))
      (node (ref "C4") (pin "2") (pinfunction "2_2") (pintype "passive"))
      (node (ref "C5") (pin "2") (pinfunction "2_2") (pintype "passive"))
      (node (ref "C6") (pin "2") (pinfunction "2_2") (pintype "passive"))
      (node (ref "C7") (pin "2") (pinfunction "2_2") (pintype "passive"))
      (node (ref "C8") (pin "2") (pinfunction "2_2") (pintype "passive"))
      (node (ref "C9") (pin "2") (pinfunction "2_2") (pintype "passive"))
      (node (ref "D2") (pin "A") (pinfunction "A_A") (pintype "passive"))
      (node (ref "E1") (pin "8") (pinfunction "GND_8") (pintype "power_in"))
      (node (ref "E10") (pin "7") (pinfunction "GND_7") (pintype "power_in"))
      (node (ref "E11") (pin "7") (pinfunction "GND_7") (pintype "power_in"))
      (node (ref "E12") (pin "7") (pinfunction "GND_7") (pintype "power_in"))
      (node (ref "E13") (pin "7") (pinfunction "GND_7") (pintype "power_in"))
      (node (ref "E14") (pin "7") (pinfunction "GND_7") (pintype "power_in"))
      (node (ref "E15") (pin "2") (pinfunction "D_2") (pintype "input"))
      (node (ref "E15") (pin "7") (pinfunction "GND_7") (pintype "power_in"))
      (node (ref "E16") (pin "7") (pinfunction "GND_7") (pintype "power_in"))
      (node (ref "E17") (pin "7") (pinfunction "GND_7") (pintype "power_in"))
      (node (ref "E18") (pin "7") (pinfunction "GND_7") (pintype "power_in"))
      (node (ref "E19") (pin "7") (pinfunction "GND_7") (pintype "power_in"))
      (node (ref "E2") (pin "7") (pinfunction "GND_7") (pintype "power_in"))
      (node (ref "E3") (pin "7") (pinfunction "GND_7") (pintype "power_in"))
      (node (ref "E4") (pin "8") (pinfunction "GND_8") (pintype "power_in"))
      (node (ref "E5") (pin "2") (pinfunction "D_2") (pintype "input"))
      (node (ref "E5") (pin "7") (pinfunction "GND_7") (pintype "power_in"))
      (node (ref "E6") (pin "7") (pinfunction "GND_7") (pintype "power_in"))
      (node (ref "E7") (pin "7") (pinfunction "GND_7") (pintype "power_in"))
      (node (ref "E8") (pin "7") (pinfunction "GND_7") (pintype "power_in"))
      (node (ref "E8") (pin "9") (pinfunction "I_9") (pintype "input"))
      (node (ref "E9") (pin "7") (pinfunction "GND_7") (pintype "power_in"))
      (node (ref "R10") (pin "1") (pinfunction "1_1") (pintype "passive"))
      (node (ref "R4") (pin "1") (pinfunction "1_1") (pintype "passive"))
      (node (ref "R5") (pin "1") (pinfunction "1_1") (pintype "passive"))
      (node (ref "U$5") (pin "AC2") (pinfunction "1_AC2") (pintype "bidirectional"))
      (node (ref "U$5") (pin "AT1") (pinfunction "1_AT1") (pintype "bidirectional"))
      (node (ref "U$5") (pin "BC2") (pinfunction "1_BC2") (pintype "bidirectional"))
      (node (ref "U$5") (pin "BT1") (pinfunction "1_BT1") (pintype "bidirectional"))
    )
    (net (code "70") (name "Net-(C16-Pad+)") (class "Default")
      (node (ref "C16") (pin "+") (pinfunction "+_+") (pintype "passive"))
      (node (ref "R11") (pin "2") (pinfunction "2_2") (pintype "passive"))
      (node (ref "R9") (pin "1") (pinfunction "1_1") (pintype "passive"))
    )
    (net (code "71") (name "Net-(C22-Pad+)") (class "Default")
      (node (ref "C22") (pin "+") (pinfunction "+_+") (pintype "passive"))
      (node (ref "D1") (pin "A") (pinfunction "A_A") (pintype "passive"))
      (node (ref "R1") (pin "1") (pinfunction "1_1") (pintype "passive"))
    )
    (net (code "72") (name "Net-(E1A-Q1)") (class "Default")
      (node (ref "E1") (pin "7") (pinfunction "Q1_7") (pintype "output"))
      (node (ref "E7") (pin "6") (pinfunction "I1_6") (pintype "input"))
    )
    (net (code "73") (name "Net-(E2A-I1)") (class "Default")
      (node (ref "C19") (pin "1") (pinfunction "1_1") (pintype "passive"))
      (node (ref "D2") (pin "C") (pinfunction "C_C") (pintype "passive"))
      (node (ref "E2") (pin "2") (pinfunction "I1_2") (pintype "input"))
      (node (ref "R5") (pin "2") (pinfunction "2_2") (pintype "passive"))
    )
    (net (code "74") (name "Net-(E2B-I0)") (class "Default")
      (node (ref "E2") (pin "4") (pinfunction "I0_4") (pintype "input"))
      (node (ref "E3") (pin "8") (pinfunction "Q_8") (pintype "output"))
      (node (ref "E6") (pin "11") (pinfunction "I0_11") (pintype "input"))
    )
    (net (code "75") (name "Net-(E2B-O)") (class "Default")
      (node (ref "E2") (pin "6") (pinfunction "O_6") (pintype "output"))
      (node (ref "E2") (pin "9") (pinfunction "I0_9") (pintype "input"))
      (node (ref "E8") (pin "11") (pinfunction "I_11") (pintype "input"))
    )
    (net (code "76") (name "Net-(E2C-O)") (class "Default")
      (node (ref "E2") (pin "12") (pinfunction "I0_12") (pintype "input"))
      (node (ref "E2") (pin "8") (pinfunction "O_8") (pintype "output"))
    )
    (net (code "77") (name "Net-(E2D-O)") (class "Default")
      (node (ref "E2") (pin "11") (pinfunction "O_11") (pintype "output"))
      (node (ref "E8") (pin "1") (pinfunction "I_1") (pintype "input"))
    )
    (net (code "78") (name "Net-(E3A-P$5)") (class "Default")
      (node (ref "C22") (pin "-") (pinfunction "-_-") (pintype "passive"))
      (node (ref "E3") (pin "11") (pinfunction "P$5_11") (pintype "bidirectional"))
      (node (ref "E6") (pin "13") (pinfunction "O_13") (pintype "open_collector"))
    )
    (net (code "79") (name "Net-(E3A-P$6)") (class "Default")
      (node (ref "D1") (pin "C") (pinfunction "C_C") (pintype "passive"))
      (node (ref "E3") (pin "13") (pinfunction "P$6_13") (pintype "bidirectional"))
    )
    (net (code "80") (name "Net-(E4A-Q0)") (class "Default")
      (node (ref "E4") (pin "6") (pinfunction "Q0_6") (pintype "output"))
      (node (ref "E7") (pin "11") (pinfunction "I0_11") (pintype "input"))
    )
    (net (code "81") (name "Net-(E4A-Q1)") (class "Default")
      (node (ref "E4") (pin "7") (pinfunction "Q1_7") (pintype "output"))
      (node (ref "E7") (pin "2") (pinfunction "I0_2") (pintype "input"))
    )
    (net (code "82") (name "Net-(E4A-Q3)") (class "Default")
      (node (ref "E4") (pin "10") (pinfunction "Q3_10") (pintype "output"))
      (node (ref "E7") (pin "8") (pinfunction "I0_8") (pintype "input"))
    )
    (net (code "83") (name "Net-(E6D-I1)") (class "Default")
      (node (ref "E6") (pin "12") (pinfunction "I1_12") (pintype "input"))
      (node (ref "E8") (pin "12") (pinfunction "O_12") (pintype "output"))
    )
    (net (code "84") (name "Net-(E9C-O)") (class "Default")
      (node (ref "C19") (pin "2") (pinfunction "2_2") (pintype "passive"))
      (node (ref "C24") (pin "1") (pinfunction "1_1") (pintype "passive"))
      (node (ref "E9") (pin "8") (pinfunction "O_8") (pintype "output"))
      (node (ref "R6") (pin "1") (pinfunction "1_1") (pintype "passive"))
    )
    (net (code "85") (name "Net-(E10A-O)") (class "Default")
      (node (ref "E10") (pin "12") (pinfunction "O_12") (pintype "output"))
      (node (ref "E15") (pin "10") (pinfunction "PRE_10") (pintype "input"))
    )
    (net (code "86") (name "Net-(E10C-O)") (class "Default")
      (node (ref "E10") (pin "8") (pinfunction "O_8") (pintype "output"))
      (node (ref "E8") (pin "5") (pinfunction "I_5") (pintype "input"))
    )
    (net (code "87") (name "Net-(E11A-I0)") (class "Default")
      (node (ref "E1") (pin "9") (pinfunction "Q2_9") (pintype "output"))
      (node (ref "E11") (pin "2") (pinfunction "I0_2") (pintype "input"))
    )
    (net (code "88") (name "Net-(E11B-I1)") (class "Default")
      (node (ref "E11") (pin "6") (pinfunction "I1_6") (pintype "input"))
      (node (ref "E4") (pin "9") (pinfunction "Q2_9") (pintype "output"))
    )
    (net (code "89") (name "Net-(E11C-I0)") (class "Default")
      (node (ref "E1") (pin "10") (pinfunction "Q3_10") (pintype "output"))
      (node (ref "E11") (pin "8") (pinfunction "I0_8") (pintype "input"))
    )
    (net (code "90") (name "Net-(E11D-I1)") (class "Default")
      (node (ref "E1") (pin "6") (pinfunction "Q0_6") (pintype "output"))
      (node (ref "E11") (pin "12") (pinfunction "I1_12") (pintype "input"))
    )
    (net (code "91") (name "Net-(E12A-I0)") (class "Default")
      (node (ref "E12") (pin "1") (pinfunction "I0_1") (pintype "input"))
      (node (ref "E12") (pin "2") (pinfunction "I1_2") (pintype "input"))
      (node (ref "E12") (pin "4") (pinfunction "I2_4") (pintype "input"))
      (node (ref "E12") (pin "5") (pinfunction "I3_5") (pintype "input"))
      (node (ref "R3") (pin "2") (pinfunction "2_2") (pintype "passive"))
    )
    (net (code "92") (name "Net-(E12B-I0)") (class "Default")
      (node (ref "E12") (pin "10") (pinfunction "I1_10") (pintype "input"))
      (node (ref "E12") (pin "12") (pinfunction "I2_12") (pintype "input"))
      (node (ref "E12") (pin "13") (pinfunction "I3_13") (pintype "input"))
      (node (ref "E12") (pin "9") (pinfunction "I0_9") (pintype "input"))
      (node (ref "E8") (pin "4") (pinfunction "O_4") (pintype "output"))
    )
    (net (code "93") (name "Net-(E13A-O)") (class "Default")
      (node (ref "E13") (pin "2") (pinfunction "O_2") (pintype "output"))
      (node (ref "E13") (pin "3") (pinfunction "I_3") (pintype "input"))
    )
    (net (code "94") (name "Net-(E13D-I)") (class "Default")
      (node (ref "E13") (pin "9") (pinfunction "I_9") (pintype "input"))
      (node (ref "E14") (pin "8") (pinfunction "O_8") (pintype "output"))
    )
    (net (code "95") (name "Net-(E13D-O)") (class "Default")
      (node (ref "E13") (pin "8") (pinfunction "O_8") (pintype "output"))
      (node (ref "E9") (pin "13") (pinfunction "I1_13") (pintype "input"))
      (node (ref "E9") (pin "2") (pinfunction "I1_2") (pintype "input"))
      (node (ref "E9") (pin "4") (pinfunction "I0_4") (pintype "input"))
    )
    (net (code "96") (name "Net-(E13F-I)") (class "Default")
      (node (ref "E13") (pin "13") (pinfunction "I_13") (pintype "input"))
      (node (ref "E9") (pin "3") (pinfunction "O_3") (pintype "output"))
    )
    (net (code "97") (name "Net-(E15A-~{Q})") (class "Default")
      (node (ref "E15") (pin "6") (pinfunction "~{Q}_6") (pintype "output"))
      (node (ref "E17") (pin "9") (pinfunction "I_9") (pintype "input"))
    )
    (net (code "98") (name "Net-(E16A-I1)") (class "Default")
      (node (ref "E16") (pin "2") (pinfunction "I1_2") (pintype "input"))
      (node (ref "E17") (pin "11") (pinfunction "I_11") (pintype "input"))
      (node (ref "E18") (pin "8") (pinfunction "~{Q}_8") (pintype "output"))
    )
    (net (code "99") (name "Net-(E16A-O)") (class "Default")
      (node (ref "E16") (pin "3") (pinfunction "O_3") (pintype "output"))
      (node (ref "E16") (pin "4") (pinfunction "I0_4") (pintype "input"))
    )
    (net (code "100") (name "Net-(E16B-I1)") (class "Default")
      (node (ref "E16") (pin "5") (pinfunction "I1_5") (pintype "input"))
      (node (ref "E19") (pin "6") (pinfunction "O_6") (pintype "output"))
    )
    (net (code "101") (name "Net-(E16D-O)") (class "Default")
      (node (ref "E16") (pin "11") (pinfunction "O_11") (pintype "output"))
      (node (ref "R3") (pin "1") (pinfunction "1_1") (pintype "passive"))
    )
    (net (code "102") (name "Net-(E17A-I)") (class "Default")
      (node (ref "E17") (pin "1") (pinfunction "I_1") (pintype "input"))
      (node (ref "E18") (pin "2") (pinfunction "D_2") (pintype "input"))
      (node (ref "E18") (pin "9") (pinfunction "Q_9") (pintype "output"))
      (node (ref "E19") (pin "4") (pinfunction "I0_4") (pintype "input"))
    )
    (net (code "103") (name "Net-(E17B-I)") (class "Default")
      (node (ref "E17") (pin "3") (pinfunction "I_3") (pintype "input"))
      (node (ref "E18") (pin "5") (pinfunction "Q_5") (pintype "output"))
      (node (ref "E19") (pin "5") (pinfunction "I1_5") (pintype "input"))
    )
    (net (code "104") (name "Net-(E17F-I)") (class "Default")
      (node (ref "E17") (pin "13") (pinfunction "I_13") (pintype "input"))
      (node (ref "Q1") (pin "2") (pinfunction "B_2") (pintype "passive"))
      (node (ref "Q2") (pin "3") (pinfunction "C_3") (pintype "passive"))
      (node (ref "R12") (pin "1") (pinfunction "1_1") (pintype "passive"))
    )
    (net (code "105") (name "Net-(E17F-O)") (class "Default")
      (node (ref "E17") (pin "12") (pinfunction "O_12") (pintype "output"))
      (node (ref "E19") (pin "10") (pinfunction "I1_10") (pintype "input"))
      (node (ref "E3") (pin "1") (pinfunction "P$1_1") (pintype "input"))
      (node (ref "E3") (pin "2") (pinfunction "P$2_2") (pintype "input"))
      (node (ref "R15") (pin "1") (pinfunction "1_1") (pintype "passive"))
      (node (ref "R16") (pin "1") (pinfunction "1_1") (pintype "passive"))
    )
    (net (code "106") (name "Net-(E19C-I0)") (class "Default")
      (node (ref "E19") (pin "11") (pinfunction "O_11") (pintype "output"))
      (node (ref "E19") (pin "9") (pinfunction "I0_9") (pintype "input"))
      (node (ref "E8") (pin "13") (pinfunction "I_13") (pintype "input"))
    )
    (net (code "107") (name "Net-(E19C-O)") (class "Default")
      (node (ref "E19") (pin "12") (pinfunction "I0_12") (pintype "input"))
      (node (ref "E19") (pin "8") (pinfunction "O_8") (pintype "output"))
    )
    (net (code "108") (name "Net-(Q1-C)") (class "Default")
      (node (ref "Q1") (pin "3") (pinfunction "C_3") (pintype "passive"))
      (node (ref "R13") (pin "1") (pinfunction "1_1") (pintype "passive"))
    )
    (net (code "109") (name "Net-(Q1-E)") (class "Default")
      (node (ref "Q1") (pin "1") (pinfunction "E_1") (pintype "passive"))
      (node (ref "Q2") (pin "1") (pinfunction "E_1") (pintype "passive"))
      (node (ref "R10") (pin "2") (pinfunction "2_2") (pintype "passive"))
    )
    (net (code "110") (name "Net-(Q2-B)") (class "Default")
      (node (ref "Q2") (pin "2") (pinfunction "B_2") (pintype "passive"))
      (node (ref "R9") (pin "2") (pinfunction "2_2") (pintype "passive"))
    )
    (net (code "111") (name "unconnected-(E3A-~{Q}-Pad6)") (class "Default")
      (node (ref "E3") (pin "6") (pinfunction "~{Q}_6") (pintype "output"))
    )
    (net (code "112") (name "unconnected-(E5B-~{Q}-Pad8)") (class "Default")
      (node (ref "E5") (pin "8") (pinfunction "~{Q}_8") (pintype "output"))
    )
    (net (code "113") (name "unconnected-(E12B-O-Pad8)") (class "Default")
      (node (ref "E12") (pin "8") (pinfunction "O_8") (pintype "output"))
    )
    (net (code "114") (name "unconnected-(E15A-Q-Pad5)") (class "Default")
      (node (ref "E15") (pin "5") (pinfunction "Q_5") (pintype "output"))
    )
  )
)
